# Mega_interface.net
KiCad netlist of a schematic drawn in EAGLE
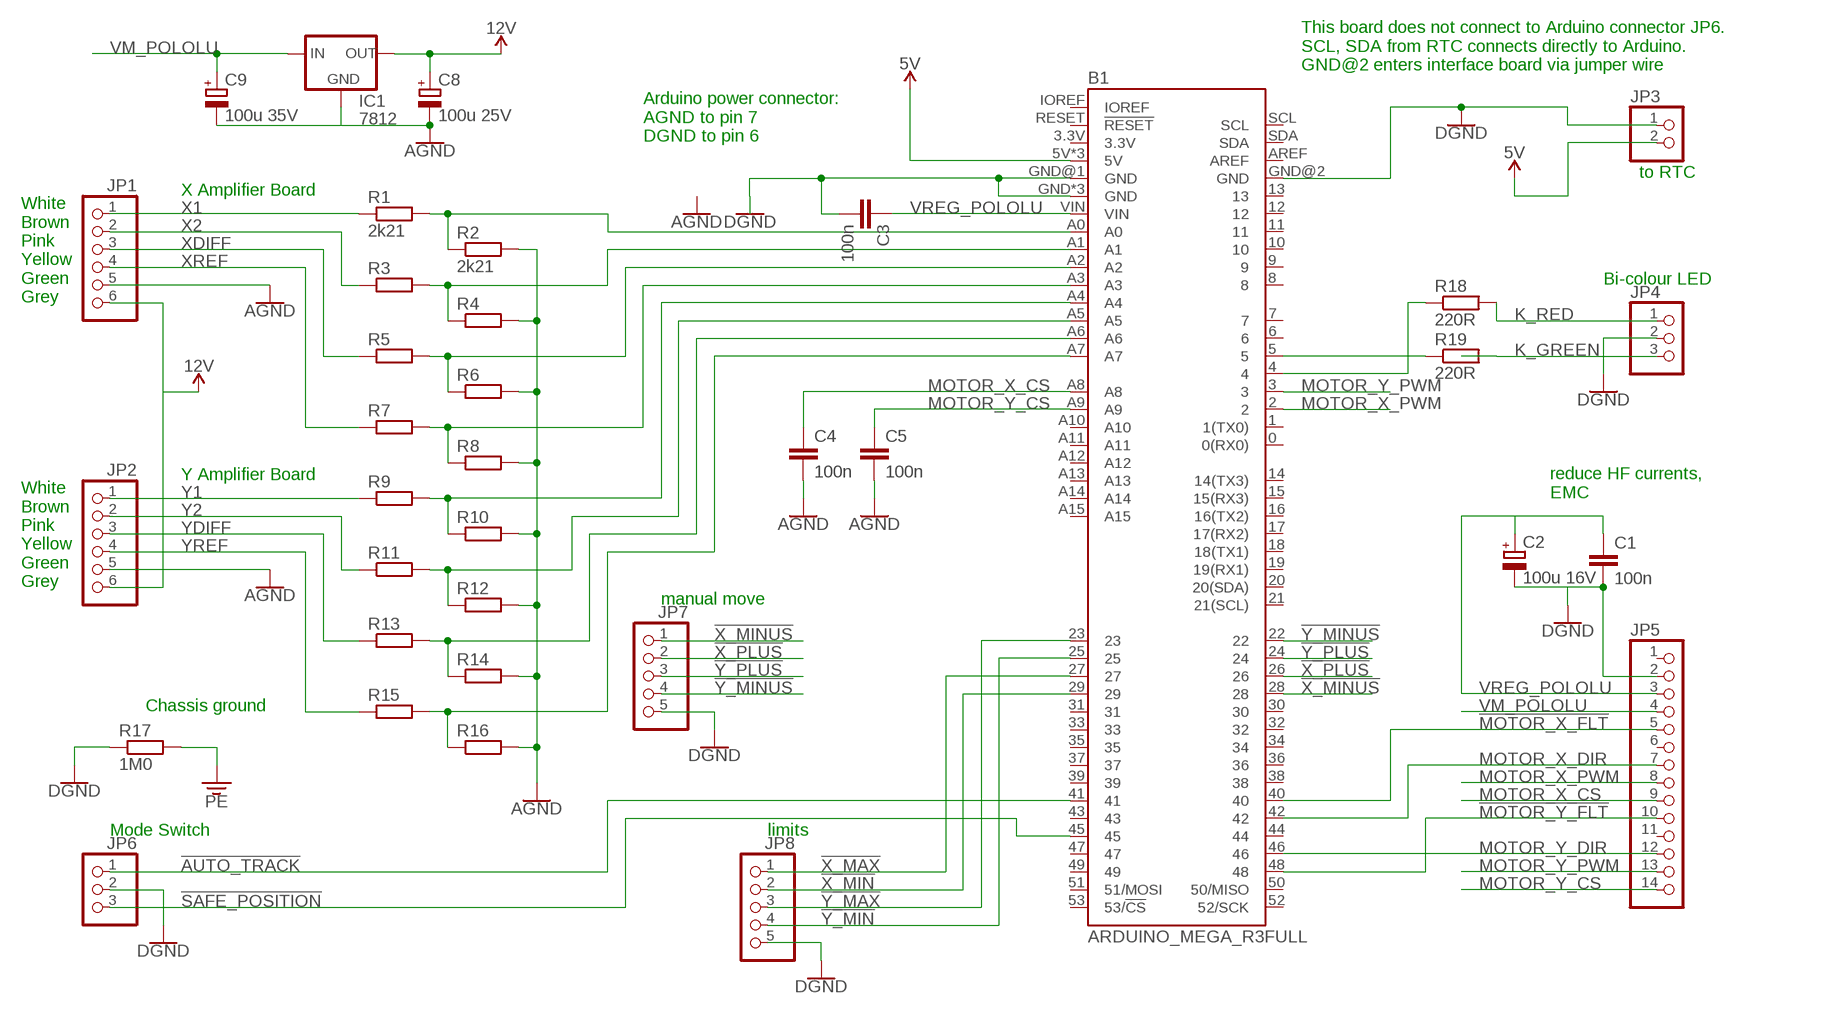
[diagram p0: schematic, sheet 1]

(export (version "E")
  (design (tool "Eeschema 10.0.6"))
  (components
    (comp (ref "B1")
      (value "ARDUINO_MEGA_R3FULL")
      (footprint "eagle-import:ARDUINO_MEGA_NO_SILK")
      (libsource (lib "eagle-import") (part "ARDUINO_MEGA_R3FULL"))
    )
    (comp (ref "C1")
      (value "100n")
      (footprint "eagle-import:C050-024X044")
      (libsource (lib "eagle-import") (part "C-EU050-024X044"))
    )
    (comp (ref "C2")
      (value "100u 16V")
      (footprint "eagle-import:B45181B")
      (libsource (lib "eagle-import") (part "CPOL-EUB45181B"))
    )
    (comp (ref "C3")
      (value "100n")
      (footprint "eagle-import:C050-024X044")
      (libsource (lib "eagle-import") (part "C-EU050-024X044"))
    )
    (comp (ref "C4")
      (value "100n")
      (footprint "eagle-import:C050-024X044")
      (libsource (lib "eagle-import") (part "C-EU050-024X044"))
    )
    (comp (ref "C5")
      (value "100n")
      (footprint "eagle-import:C050-024X044")
      (libsource (lib "eagle-import") (part "C-EU050-024X044"))
    )
    (comp (ref "C8")
      (value "100u 25V")
      (footprint "eagle-import:B45181B")
      (libsource (lib "eagle-import") (part "CPOL-EUB45181B"))
    )
    (comp (ref "C9")
      (value "100u 35V")
      (footprint "eagle-import:B45181B")
      (libsource (lib "eagle-import") (part "CPOL-EUB45181B"))
    )
    (comp (ref "IC1")
      (value "7812")
      (footprint "eagle-import:78XXL")
      (libsource (lib "eagle-import") (part "78XXL"))
    )
    (comp (ref "JP1")
      (value "PINHD-1X6")
      (footprint "eagle-import:1X06")
      (libsource (lib "eagle-import") (part "PINHD-1X6"))
    )
    (comp (ref "JP2")
      (value "PINHD-1X6")
      (footprint "eagle-import:1X06")
      (libsource (lib "eagle-import") (part "PINHD-1X6"))
    )
    (comp (ref "JP3")
      (value "PINHD-1X2")
      (footprint "eagle-import:1X02")
      (libsource (lib "eagle-import") (part "PINHD-1X2"))
    )
    (comp (ref "JP4")
      (value "PINHD-1X3")
      (footprint "eagle-import:1X03")
      (libsource (lib "eagle-import") (part "PINHD-1X3"))
    )
    (comp (ref "JP5")
      (value "PINHD-1X14")
      (footprint "eagle-import:1X14")
      (libsource (lib "eagle-import") (part "PINHD-1X14"))
    )
    (comp (ref "JP6")
      (value "PINHD-1X3")
      (footprint "eagle-import:1X03")
      (libsource (lib "eagle-import") (part "PINHD-1X3"))
    )
    (comp (ref "JP7")
      (value "PINHD-1X5")
      (footprint "eagle-import:1X05")
      (libsource (lib "eagle-import") (part "PINHD-1X5"))
    )
    (comp (ref "JP8")
      (value "PINHD-1X5")
      (footprint "eagle-import:1X05")
      (libsource (lib "eagle-import") (part "PINHD-1X5"))
    )
    (comp (ref "R1")
      (value "2k21")
      (footprint "eagle-import:0207_10")
      (libsource (lib "eagle-import") (part "R-EU_0207/10"))
    )
    (comp (ref "R2")
      (value "2k21")
      (footprint "eagle-import:0207_10")
      (libsource (lib "eagle-import") (part "R-EU_0207/10"))
    )
    (comp (ref "R3")
      (value "R-EU_0207/10")
      (footprint "eagle-import:0207_10")
      (libsource (lib "eagle-import") (part "R-EU_0207/10"))
    )
    (comp (ref "R4")
      (value "R-EU_0207/10")
      (footprint "eagle-import:0207_10")
      (libsource (lib "eagle-import") (part "R-EU_0207/10"))
    )
    (comp (ref "R5")
      (value "R-EU_0207/10")
      (footprint "eagle-import:0207_10")
      (libsource (lib "eagle-import") (part "R-EU_0207/10"))
    )
    (comp (ref "R6")
      (value "R-EU_0207/10")
      (footprint "eagle-import:0207_10")
      (libsource (lib "eagle-import") (part "R-EU_0207/10"))
    )
    (comp (ref "R7")
      (value "R-EU_0207/10")
      (footprint "eagle-import:0207_10")
      (libsource (lib "eagle-import") (part "R-EU_0207/10"))
    )
    (comp (ref "R8")
      (value "R-EU_0207/10")
      (footprint "eagle-import:0207_10")
      (libsource (lib "eagle-import") (part "R-EU_0207/10"))
    )
    (comp (ref "R9")
      (value "R-EU_0207/10")
      (footprint "eagle-import:0207_10")
      (libsource (lib "eagle-import") (part "R-EU_0207/10"))
    )
    (comp (ref "R10")
      (value "R-EU_0207/10")
      (footprint "eagle-import:0207_10")
      (libsource (lib "eagle-import") (part "R-EU_0207/10"))
    )
    (comp (ref "R11")
      (value "R-EU_0207/10")
      (footprint "eagle-import:0207_10")
      (libsource (lib "eagle-import") (part "R-EU_0207/10"))
    )
    (comp (ref "R12")
      (value "R-EU_0207/10")
      (footprint "eagle-import:0207_10")
      (libsource (lib "eagle-import") (part "R-EU_0207/10"))
    )
    (comp (ref "R13")
      (value "R-EU_0207/10")
      (footprint "eagle-import:0207_10")
      (libsource (lib "eagle-import") (part "R-EU_0207/10"))
    )
    (comp (ref "R14")
      (value "R-EU_0207/10")
      (footprint "eagle-import:0207_10")
      (libsource (lib "eagle-import") (part "R-EU_0207/10"))
    )
    (comp (ref "R15")
      (value "R-EU_0207/10")
      (footprint "eagle-import:0207_10")
      (libsource (lib "eagle-import") (part "R-EU_0207/10"))
    )
    (comp (ref "R16")
      (value "R-EU_0207/10")
      (footprint "eagle-import:0207_10")
      (libsource (lib "eagle-import") (part "R-EU_0207/10"))
    )
    (comp (ref "R17")
      (value "1M0")
      (footprint "eagle-import:0207_10")
      (libsource (lib "eagle-import") (part "R-EU_0207/10"))
    )
    (comp (ref "R18")
      (value "220R")
      (footprint "eagle-import:0207_10")
      (libsource (lib "eagle-import") (part "R-EU_0207/10"))
    )
    (comp (ref "R19")
      (value "220R")
      (footprint "eagle-import:0207_10")
      (libsource (lib "eagle-import") (part "R-EU_0207/10"))
    )
  )
  (nets
    (net (code "1") (name "/K_GREEN") (class "Default")
      (node (ref "JP4") (pin "3") (pinfunction "3_3") (pintype "passive"))
      (node (ref "R19") (pin "2") (pinfunction "2_2") (pintype "passive"))
    )
    (net (code "2") (name "/K_RED") (class "Default")
      (node (ref "JP4") (pin "1") (pinfunction "1_1") (pintype "passive"))
      (node (ref "R18") (pin "2") (pinfunction "2_2") (pintype "passive"))
    )
    (net (code "3") (name "/MOTOR_X_CS") (class "Default")
      (node (ref "B1") (pin "A8") (pinfunction "A8_A8") (pintype "bidirectional"))
      (node (ref "C4") (pin "1") (pinfunction "1_1") (pintype "passive"))
      (node (ref "JP5") (pin "9") (pinfunction "9_9") (pintype "passive"))
    )
    (net (code "4") (name "/MOTOR_X_DIR") (class "Default")
      (node (ref "B1") (pin "42") (pinfunction "42_42") (pintype "bidirectional"))
      (node (ref "JP5") (pin "7") (pinfunction "7_7") (pintype "passive"))
    )
    (net (code "5") (name "/MOTOR_X_PWM") (class "Default")
      (node (ref "B1") (pin "2") (pinfunction "2_2") (pintype "bidirectional"))
      (node (ref "JP5") (pin "8") (pinfunction "8_8") (pintype "passive"))
    )
    (net (code "6") (name "/MOTOR_Y_CS") (class "Default")
      (node (ref "B1") (pin "A9") (pinfunction "A9_A9") (pintype "bidirectional"))
      (node (ref "C5") (pin "1") (pinfunction "1_1") (pintype "passive"))
      (node (ref "JP5") (pin "14") (pinfunction "14_14") (pintype "passive"))
    )
    (net (code "7") (name "/MOTOR_Y_DIR") (class "Default")
      (node (ref "B1") (pin "46") (pinfunction "46_46") (pintype "bidirectional"))
      (node (ref "JP5") (pin "12") (pinfunction "12_12") (pintype "passive"))
    )
    (net (code "8") (name "/MOTOR_Y_PWM") (class "Default")
      (node (ref "B1") (pin "3") (pinfunction "3_3") (pintype "bidirectional"))
      (node (ref "JP5") (pin "13") (pinfunction "13_13") (pintype "passive"))
    )
    (net (code "9") (name "/VM_POLOLU") (class "Default")
      (node (ref "C9") (pin "+") (pinfunction "+_+") (pintype "passive"))
      (node (ref "IC1") (pin "IN") (pinfunction "IN_IN") (pintype "input"))
      (node (ref "JP5") (pin "4") (pinfunction "4_4") (pintype "passive"))
    )
    (net (code "10") (name "/VREG_POLOLU") (class "Default")
      (node (ref "B1") (pin "VIN") (pinfunction "VIN_VIN") (pintype "bidirectional"))
      (node (ref "C1") (pin "1") (pinfunction "1_1") (pintype "passive"))
      (node (ref "C2") (pin "+") (pinfunction "+_+") (pintype "passive"))
      (node (ref "C3") (pin "1") (pinfunction "1_1") (pintype "passive"))
      (node (ref "JP5") (pin "3") (pinfunction "3_3") (pintype "passive"))
    )
    (net (code "11") (name "/X1") (class "Default")
      (node (ref "JP1") (pin "1") (pinfunction "1_1") (pintype "passive"))
      (node (ref "R1") (pin "1") (pinfunction "1_1") (pintype "passive"))
    )
    (net (code "12") (name "/X2") (class "Default")
      (node (ref "JP1") (pin "2") (pinfunction "2_2") (pintype "passive"))
      (node (ref "R3") (pin "1") (pinfunction "1_1") (pintype "passive"))
    )
    (net (code "13") (name "/XDIFF") (class "Default")
      (node (ref "JP1") (pin "3") (pinfunction "3_3") (pintype "passive"))
      (node (ref "R5") (pin "1") (pinfunction "1_1") (pintype "passive"))
    )
    (net (code "14") (name "/XREF") (class "Default")
      (node (ref "JP1") (pin "4") (pinfunction "4_4") (pintype "passive"))
      (node (ref "R7") (pin "1") (pinfunction "1_1") (pintype "passive"))
    )
    (net (code "15") (name "/Y1") (class "Default")
      (node (ref "JP2") (pin "1") (pinfunction "1_1") (pintype "passive"))
      (node (ref "R9") (pin "1") (pinfunction "1_1") (pintype "passive"))
    )
    (net (code "16") (name "/Y2") (class "Default")
      (node (ref "JP2") (pin "2") (pinfunction "2_2") (pintype "passive"))
      (node (ref "R11") (pin "1") (pinfunction "1_1") (pintype "passive"))
    )
    (net (code "17") (name "/YDIFF") (class "Default")
      (node (ref "JP2") (pin "3") (pinfunction "3_3") (pintype "passive"))
      (node (ref "R13") (pin "1") (pinfunction "1_1") (pintype "passive"))
    )
    (net (code "18") (name "/YREF") (class "Default")
      (node (ref "JP2") (pin "4") (pinfunction "4_4") (pintype "passive"))
      (node (ref "R15") (pin "1") (pinfunction "1_1") (pintype "passive"))
    )
    (net (code "19") (name "/~{AUTO_TRACK}") (class "Default")
      (node (ref "B1") (pin "41") (pinfunction "41_41") (pintype "bidirectional"))
      (node (ref "JP6") (pin "1") (pinfunction "1_1") (pintype "passive"))
    )
    (net (code "20") (name "/~{MOTOR_X_FLT}") (class "Default")
      (node (ref "B1") (pin "40") (pinfunction "40_40") (pintype "bidirectional"))
      (node (ref "JP5") (pin "5") (pinfunction "5_5") (pintype "passive"))
    )
    (net (code "21") (name "/~{MOTOR_Y_FLT}") (class "Default")
      (node (ref "B1") (pin "48") (pinfunction "48_48") (pintype "bidirectional"))
      (node (ref "JP5") (pin "10") (pinfunction "10_10") (pintype "passive"))
    )
    (net (code "22") (name "/~{SAFE_POSITION}") (class "Default")
      (node (ref "B1") (pin "45") (pinfunction "45_45") (pintype "bidirectional"))
      (node (ref "JP6") (pin "3") (pinfunction "3_3") (pintype "passive"))
    )
    (net (code "23") (name "/~{X_MAX}") (class "Default")
      (node (ref "B1") (pin "27") (pinfunction "27_27") (pintype "bidirectional"))
      (node (ref "JP8") (pin "1") (pinfunction "1_1") (pintype "passive"))
    )
    (net (code "24") (name "/~{X_MINUS}") (class "Default")
      (node (ref "B1") (pin "28") (pinfunction "28_28") (pintype "bidirectional"))
      (node (ref "JP7") (pin "1") (pinfunction "1_1") (pintype "passive"))
    )
    (net (code "25") (name "/~{X_MIN}") (class "Default")
      (node (ref "B1") (pin "29") (pinfunction "29_29") (pintype "bidirectional"))
      (node (ref "JP8") (pin "2") (pinfunction "2_2") (pintype "passive"))
    )
    (net (code "26") (name "/~{X_PLUS}") (class "Default")
      (node (ref "B1") (pin "26") (pinfunction "26_26") (pintype "bidirectional"))
      (node (ref "JP7") (pin "2") (pinfunction "2_2") (pintype "passive"))
    )
    (net (code "27") (name "/~{Y_MAX}") (class "Default")
      (node (ref "B1") (pin "23") (pinfunction "23_23") (pintype "bidirectional"))
      (node (ref "JP8") (pin "3") (pinfunction "3_3") (pintype "passive"))
    )
    (net (code "28") (name "/~{Y_MINUS}") (class "Default")
      (node (ref "B1") (pin "22") (pinfunction "22_22") (pintype "bidirectional"))
      (node (ref "JP7") (pin "4") (pinfunction "4_4") (pintype "passive"))
    )
    (net (code "29") (name "/~{Y_MIN}") (class "Default")
      (node (ref "B1") (pin "25") (pinfunction "25_25") (pintype "bidirectional"))
      (node (ref "JP8") (pin "4") (pinfunction "4_4") (pintype "passive"))
    )
    (net (code "30") (name "/~{Y_PLUS}") (class "Default")
      (node (ref "B1") (pin "24") (pinfunction "24_24") (pintype "bidirectional"))
      (node (ref "JP7") (pin "3") (pinfunction "3_3") (pintype "passive"))
    )
    (net (code "31") (name "5V") (class "Default")
      (node (ref "B1") (pin "5V") (pinfunction "5V_5V") (pintype "bidirectional"))
      (node (ref "B1") (pin "5V@1") (pinfunction "5V_5V@1") (pintype "bidirectional"))
      (node (ref "B1") (pin "5V@2") (pinfunction "5V_5V@2") (pintype "bidirectional"))
      (node (ref "JP3") (pin "2") (pinfunction "2_2") (pintype "passive"))
    )
    (net (code "32") (name "12V") (class "Default")
      (node (ref "C8") (pin "+") (pinfunction "+_+") (pintype "passive"))
      (node (ref "IC1") (pin "OUT") (pinfunction "OUT_OUT") (pintype "passive"))
      (node (ref "JP1") (pin "6") (pinfunction "6_6") (pintype "passive"))
      (node (ref "JP2") (pin "6") (pinfunction "6_6") (pintype "passive"))
    )
    (net (code "33") (name "AGND") (class "Default")
      (node (ref "C4") (pin "2") (pinfunction "2_2") (pintype "passive"))
      (node (ref "C5") (pin "2") (pinfunction "2_2") (pintype "passive"))
      (node (ref "C8") (pin "-") (pinfunction "-_-") (pintype "passive"))
      (node (ref "C9") (pin "-") (pinfunction "-_-") (pintype "passive"))
      (node (ref "IC1") (pin "GND") (pinfunction "GND_GND") (pintype "input"))
      (node (ref "JP1") (pin "5") (pinfunction "5_5") (pintype "passive"))
      (node (ref "JP2") (pin "5") (pinfunction "5_5") (pintype "passive"))
      (node (ref "R10") (pin "2") (pinfunction "2_2") (pintype "passive"))
      (node (ref "R12") (pin "2") (pinfunction "2_2") (pintype "passive"))
      (node (ref "R14") (pin "2") (pinfunction "2_2") (pintype "passive"))
      (node (ref "R16") (pin "2") (pinfunction "2_2") (pintype "passive"))
      (node (ref "R2") (pin "2") (pinfunction "2_2") (pintype "passive"))
      (node (ref "R4") (pin "2") (pinfunction "2_2") (pintype "passive"))
      (node (ref "R6") (pin "2") (pinfunction "2_2") (pintype "passive"))
      (node (ref "R8") (pin "2") (pinfunction "2_2") (pintype "passive"))
    )
    (net (code "34") (name "DGND") (class "Default")
      (node (ref "B1") (pin "GND") (pinfunction "GND_GND") (pintype "bidirectional"))
      (node (ref "B1") (pin "GND@1") (pinfunction "GND_GND@1") (pintype "bidirectional"))
      (node (ref "B1") (pin "GND@2") (pinfunction "GND_GND@2") (pintype "bidirectional"))
      (node (ref "B1") (pin "GND@3") (pinfunction "GND_GND@3") (pintype "bidirectional"))
      (node (ref "B1") (pin "GND@4") (pinfunction "GND_GND@4") (pintype "bidirectional"))
      (node (ref "C1") (pin "2") (pinfunction "2_2") (pintype "passive"))
      (node (ref "C2") (pin "-") (pinfunction "-_-") (pintype "passive"))
      (node (ref "C3") (pin "2") (pinfunction "2_2") (pintype "passive"))
      (node (ref "JP3") (pin "1") (pinfunction "1_1") (pintype "passive"))
      (node (ref "JP4") (pin "2") (pinfunction "2_2") (pintype "passive"))
      (node (ref "JP5") (pin "2") (pinfunction "2_2") (pintype "passive"))
      (node (ref "JP6") (pin "2") (pinfunction "2_2") (pintype "passive"))
      (node (ref "JP7") (pin "5") (pinfunction "5_5") (pintype "passive"))
      (node (ref "JP8") (pin "5") (pinfunction "5_5") (pintype "passive"))
      (node (ref "R17") (pin "1") (pinfunction "1_1") (pintype "passive"))
    )
    (net (code "35") (name "Net-(B1-Pad4)") (class "Default")
      (node (ref "B1") (pin "4") (pinfunction "4_4") (pintype "bidirectional"))
      (node (ref "R18") (pin "1") (pinfunction "1_1") (pintype "passive"))
    )
    (net (code "36") (name "Net-(B1-Pad5)") (class "Default")
      (node (ref "B1") (pin "5") (pinfunction "5_5") (pintype "bidirectional"))
      (node (ref "R19") (pin "1") (pinfunction "1_1") (pintype "passive"))
    )
    (net (code "37") (name "Net-(B1-PadA0)") (class "Default")
      (node (ref "B1") (pin "A0") (pinfunction "A0_A0") (pintype "bidirectional"))
      (node (ref "R1") (pin "2") (pinfunction "2_2") (pintype "passive"))
      (node (ref "R2") (pin "1") (pinfunction "1_1") (pintype "passive"))
    )
    (net (code "38") (name "Net-(B1-PadA1)") (class "Default")
      (node (ref "B1") (pin "A1") (pinfunction "A1_A1") (pintype "bidirectional"))
      (node (ref "R3") (pin "2") (pinfunction "2_2") (pintype "passive"))
      (node (ref "R4") (pin "1") (pinfunction "1_1") (pintype "passive"))
    )
    (net (code "39") (name "Net-(B1-PadA2)") (class "Default")
      (node (ref "B1") (pin "A2") (pinfunction "A2_A2") (pintype "bidirectional"))
      (node (ref "R5") (pin "2") (pinfunction "2_2") (pintype "passive"))
      (node (ref "R6") (pin "1") (pinfunction "1_1") (pintype "passive"))
    )
    (net (code "40") (name "Net-(B1-PadA3)") (class "Default")
      (node (ref "B1") (pin "A3") (pinfunction "A3_A3") (pintype "bidirectional"))
      (node (ref "R7") (pin "2") (pinfunction "2_2") (pintype "passive"))
      (node (ref "R8") (pin "1") (pinfunction "1_1") (pintype "passive"))
    )
    (net (code "41") (name "Net-(B1-PadA4)") (class "Default")
      (node (ref "B1") (pin "A4") (pinfunction "A4_A4") (pintype "bidirectional"))
      (node (ref "R10") (pin "1") (pinfunction "1_1") (pintype "passive"))
      (node (ref "R9") (pin "2") (pinfunction "2_2") (pintype "passive"))
    )
    (net (code "42") (name "Net-(B1-PadA5)") (class "Default")
      (node (ref "B1") (pin "A5") (pinfunction "A5_A5") (pintype "bidirectional"))
      (node (ref "R11") (pin "2") (pinfunction "2_2") (pintype "passive"))
      (node (ref "R12") (pin "1") (pinfunction "1_1") (pintype "passive"))
    )
    (net (code "43") (name "Net-(B1-PadA6)") (class "Default")
      (node (ref "B1") (pin "A6") (pinfunction "A6_A6") (pintype "bidirectional"))
      (node (ref "R13") (pin "2") (pinfunction "2_2") (pintype "passive"))
      (node (ref "R14") (pin "1") (pinfunction "1_1") (pintype "passive"))
    )
    (net (code "44") (name "Net-(B1-PadA7)") (class "Default")
      (node (ref "B1") (pin "A7") (pinfunction "A7_A7") (pintype "bidirectional"))
      (node (ref "R15") (pin "2") (pinfunction "2_2") (pintype "passive"))
      (node (ref "R16") (pin "1") (pinfunction "1_1") (pintype "passive"))
    )
    (net (code "45") (name "PE") (class "Default")
      (node (ref "R17") (pin "2") (pinfunction "2_2") (pintype "passive"))
    )
    (net (code "46") (name "unconnected-(B1-0(RX0)-Pad0)") (class "Default")
      (node (ref "B1") (pin "0") (pinfunction "0(RX0)_0") (pintype "bidirectional"))
    )
    (net (code "47") (name "unconnected-(B1-1(TX0)-Pad1)") (class "Default")
      (node (ref "B1") (pin "1") (pinfunction "1(TX0)_1") (pintype "bidirectional"))
    )
    (net (code "48") (name "unconnected-(B1-14(TX3)-Pad14)") (class "Default")
      (node (ref "B1") (pin "14") (pinfunction "14(TX3)_14") (pintype "bidirectional"))
    )
    (net (code "49") (name "unconnected-(B1-15(RX3)-Pad15)") (class "Default")
      (node (ref "B1") (pin "15") (pinfunction "15(RX3)_15") (pintype "bidirectional"))
    )
    (net (code "50") (name "unconnected-(B1-16(TX2)-Pad16)") (class "Default")
      (node (ref "B1") (pin "16") (pinfunction "16(TX2)_16") (pintype "bidirectional"))
    )
    (net (code "51") (name "unconnected-(B1-17(RX2)-Pad17)") (class "Default")
      (node (ref "B1") (pin "17") (pinfunction "17(RX2)_17") (pintype "bidirectional"))
    )
    (net (code "52") (name "unconnected-(B1-18(TX1)-Pad18)") (class "Default")
      (node (ref "B1") (pin "18") (pinfunction "18(TX1)_18") (pintype "bidirectional"))
    )
    (net (code "53") (name "unconnected-(B1-19(RX1)-Pad19)") (class "Default")
      (node (ref "B1") (pin "19") (pinfunction "19(RX1)_19") (pintype "bidirectional"))
    )
    (net (code "54") (name "unconnected-(B1-20(SDA)-Pad20)") (class "Default")
      (node (ref "B1") (pin "20") (pinfunction "20(SDA)_20") (pintype "bidirectional"))
    )
    (net (code "55") (name "unconnected-(B1-21(SCL)-Pad21)") (class "Default")
      (node (ref "B1") (pin "21") (pinfunction "21(SCL)_21") (pintype "bidirectional"))
    )
    (net (code "56") (name "unconnected-(B1-50{slash}MISO-Pad50)") (class "Default")
      (node (ref "B1") (pin "50") (pinfunction "50/MISO_50") (pintype "bidirectional"))
    )
    (net (code "57") (name "unconnected-(B1-51{slash}MOSI-Pad51)") (class "Default")
      (node (ref "B1") (pin "51") (pinfunction "51/MOSI_51") (pintype "bidirectional"))
    )
    (net (code "58") (name "unconnected-(B1-52{slash}SCK-Pad52)") (class "Default")
      (node (ref "B1") (pin "52") (pinfunction "52/SCK_52") (pintype "bidirectional"))
    )
    (net (code "59") (name "unconnected-(B1-53{slash}~{CS}-Pad53)") (class "Default")
      (node (ref "B1") (pin "53") (pinfunction "53/~{CS}_53") (pintype "bidirectional"))
    )
    (net (code "60") (name "unconnected-(B1-Pad3.3V)") (class "Default")
      (node (ref "B1") (pin "3.3V") (pinfunction "3.3V_3.3V") (pintype "bidirectional"))
    )
    (net (code "61") (name "unconnected-(B1-Pad6)") (class "Default")
      (node (ref "B1") (pin "6") (pinfunction "6_6") (pintype "bidirectional"))
    )
    (net (code "62") (name "unconnected-(B1-Pad7)") (class "Default")
      (node (ref "B1") (pin "7") (pinfunction "7_7") (pintype "bidirectional"))
    )
    (net (code "63") (name "unconnected-(B1-Pad8)") (class "Default")
      (node (ref "B1") (pin "8") (pinfunction "8_8") (pintype "bidirectional"))
    )
    (net (code "64") (name "unconnected-(B1-Pad9)") (class "Default")
      (node (ref "B1") (pin "9") (pinfunction "9_9") (pintype "bidirectional"))
    )
    (net (code "65") (name "unconnected-(B1-Pad10)") (class "Default")
      (node (ref "B1") (pin "10") (pinfunction "10_10") (pintype "bidirectional"))
    )
    (net (code "66") (name "unconnected-(B1-Pad11)") (class "Default")
      (node (ref "B1") (pin "11") (pinfunction "11_11") (pintype "bidirectional"))
    )
    (net (code "67") (name "unconnected-(B1-Pad12)") (class "Default")
      (node (ref "B1") (pin "12") (pinfunction "12_12") (pintype "bidirectional"))
    )
    (net (code "68") (name "unconnected-(B1-Pad13)") (class "Default")
      (node (ref "B1") (pin "13") (pinfunction "13_13") (pintype "bidirectional"))
    )
    (net (code "69") (name "unconnected-(B1-Pad30)") (class "Default")
      (node (ref "B1") (pin "30") (pinfunction "30_30") (pintype "bidirectional"))
    )
    (net (code "70") (name "unconnected-(B1-Pad31)") (class "Default")
      (node (ref "B1") (pin "31") (pinfunction "31_31") (pintype "bidirectional"))
    )
    (net (code "71") (name "unconnected-(B1-Pad32)") (class "Default")
      (node (ref "B1") (pin "32") (pinfunction "32_32") (pintype "bidirectional"))
    )
    (net (code "72") (name "unconnected-(B1-Pad33)") (class "Default")
      (node (ref "B1") (pin "33") (pinfunction "33_33") (pintype "bidirectional"))
    )
    (net (code "73") (name "unconnected-(B1-Pad34)") (class "Default")
      (node (ref "B1") (pin "34") (pinfunction "34_34") (pintype "bidirectional"))
    )
    (net (code "74") (name "unconnected-(B1-Pad35)") (class "Default")
      (node (ref "B1") (pin "35") (pinfunction "35_35") (pintype "bidirectional"))
    )
    (net (code "75") (name "unconnected-(B1-Pad36)") (class "Default")
      (node (ref "B1") (pin "36") (pinfunction "36_36") (pintype "bidirectional"))
    )
    (net (code "76") (name "unconnected-(B1-Pad37)") (class "Default")
      (node (ref "B1") (pin "37") (pinfunction "37_37") (pintype "bidirectional"))
    )
    (net (code "77") (name "unconnected-(B1-Pad38)") (class "Default")
      (node (ref "B1") (pin "38") (pinfunction "38_38") (pintype "bidirectional"))
    )
    (net (code "78") (name "unconnected-(B1-Pad39)") (class "Default")
      (node (ref "B1") (pin "39") (pinfunction "39_39") (pintype "bidirectional"))
    )
    (net (code "79") (name "unconnected-(B1-Pad43)") (class "Default")
      (node (ref "B1") (pin "43") (pinfunction "43_43") (pintype "bidirectional"))
    )
    (net (code "80") (name "unconnected-(B1-Pad44)") (class "Default")
      (node (ref "B1") (pin "44") (pinfunction "44_44") (pintype "bidirectional"))
    )
    (net (code "81") (name "unconnected-(B1-Pad47)") (class "Default")
      (node (ref "B1") (pin "47") (pinfunction "47_47") (pintype "bidirectional"))
    )
    (net (code "82") (name "unconnected-(B1-Pad49)") (class "Default")
      (node (ref "B1") (pin "49") (pinfunction "49_49") (pintype "bidirectional"))
    )
    (net (code "83") (name "unconnected-(B1-PadA10)") (class "Default")
      (node (ref "B1") (pin "A10") (pinfunction "A10_A10") (pintype "bidirectional"))
    )
    (net (code "84") (name "unconnected-(B1-PadA11)") (class "Default")
      (node (ref "B1") (pin "A11") (pinfunction "A11_A11") (pintype "bidirectional"))
    )
    (net (code "85") (name "unconnected-(B1-PadA12)") (class "Default")
      (node (ref "B1") (pin "A12") (pinfunction "A12_A12") (pintype "bidirectional"))
    )
    (net (code "86") (name "unconnected-(B1-PadA13)") (class "Default")
      (node (ref "B1") (pin "A13") (pinfunction "A13_A13") (pintype "bidirectional"))
    )
    (net (code "87") (name "unconnected-(B1-PadA14)") (class "Default")
      (node (ref "B1") (pin "A14") (pinfunction "A14_A14") (pintype "bidirectional"))
    )
    (net (code "88") (name "unconnected-(B1-PadA15)") (class "Default")
      (node (ref "B1") (pin "A15") (pinfunction "A15_A15") (pintype "bidirectional"))
    )
    (net (code "89") (name "unconnected-(B1-PadAREF)") (class "Default")
      (node (ref "B1") (pin "AREF") (pinfunction "AREF_AREF") (pintype "bidirectional"))
    )
    (net (code "90") (name "unconnected-(B1-PadIOREF)") (class "Default")
      (node (ref "B1") (pin "IOREF") (pinfunction "IOREF_IOREF") (pintype "bidirectional"))
    )
    (net (code "91") (name "unconnected-(B1-PadSCL)") (class "Default")
      (node (ref "B1") (pin "SCL") (pinfunction "SCL_SCL") (pintype "bidirectional"))
    )
    (net (code "92") (name "unconnected-(B1-PadSDA)") (class "Default")
      (node (ref "B1") (pin "SDA") (pinfunction "SDA_SDA") (pintype "bidirectional"))
    )
    (net (code "93") (name "unconnected-(B1-~{RESET}-PadRESET)") (class "Default")
      (node (ref "B1") (pin "RESET") (pinfunction "~{RESET}_RESET") (pintype "bidirectional"))
    )
    (net (code "94") (name "unconnected-(JP5-Pad1)") (class "Default")
      (node (ref "JP5") (pin "1") (pinfunction "1_1") (pintype "passive"))
    )
    (net (code "95") (name "unconnected-(JP5-Pad6)") (class "Default")
      (node (ref "JP5") (pin "6") (pinfunction "6_6") (pintype "passive"))
    )
    (net (code "96") (name "unconnected-(JP5-Pad11)") (class "Default")
      (node (ref "JP5") (pin "11") (pinfunction "11_11") (pintype "passive"))
    )
  )
)
